# Mozard_2019-08-29.net
KiCad netlist of a schematic drawn in EAGLE
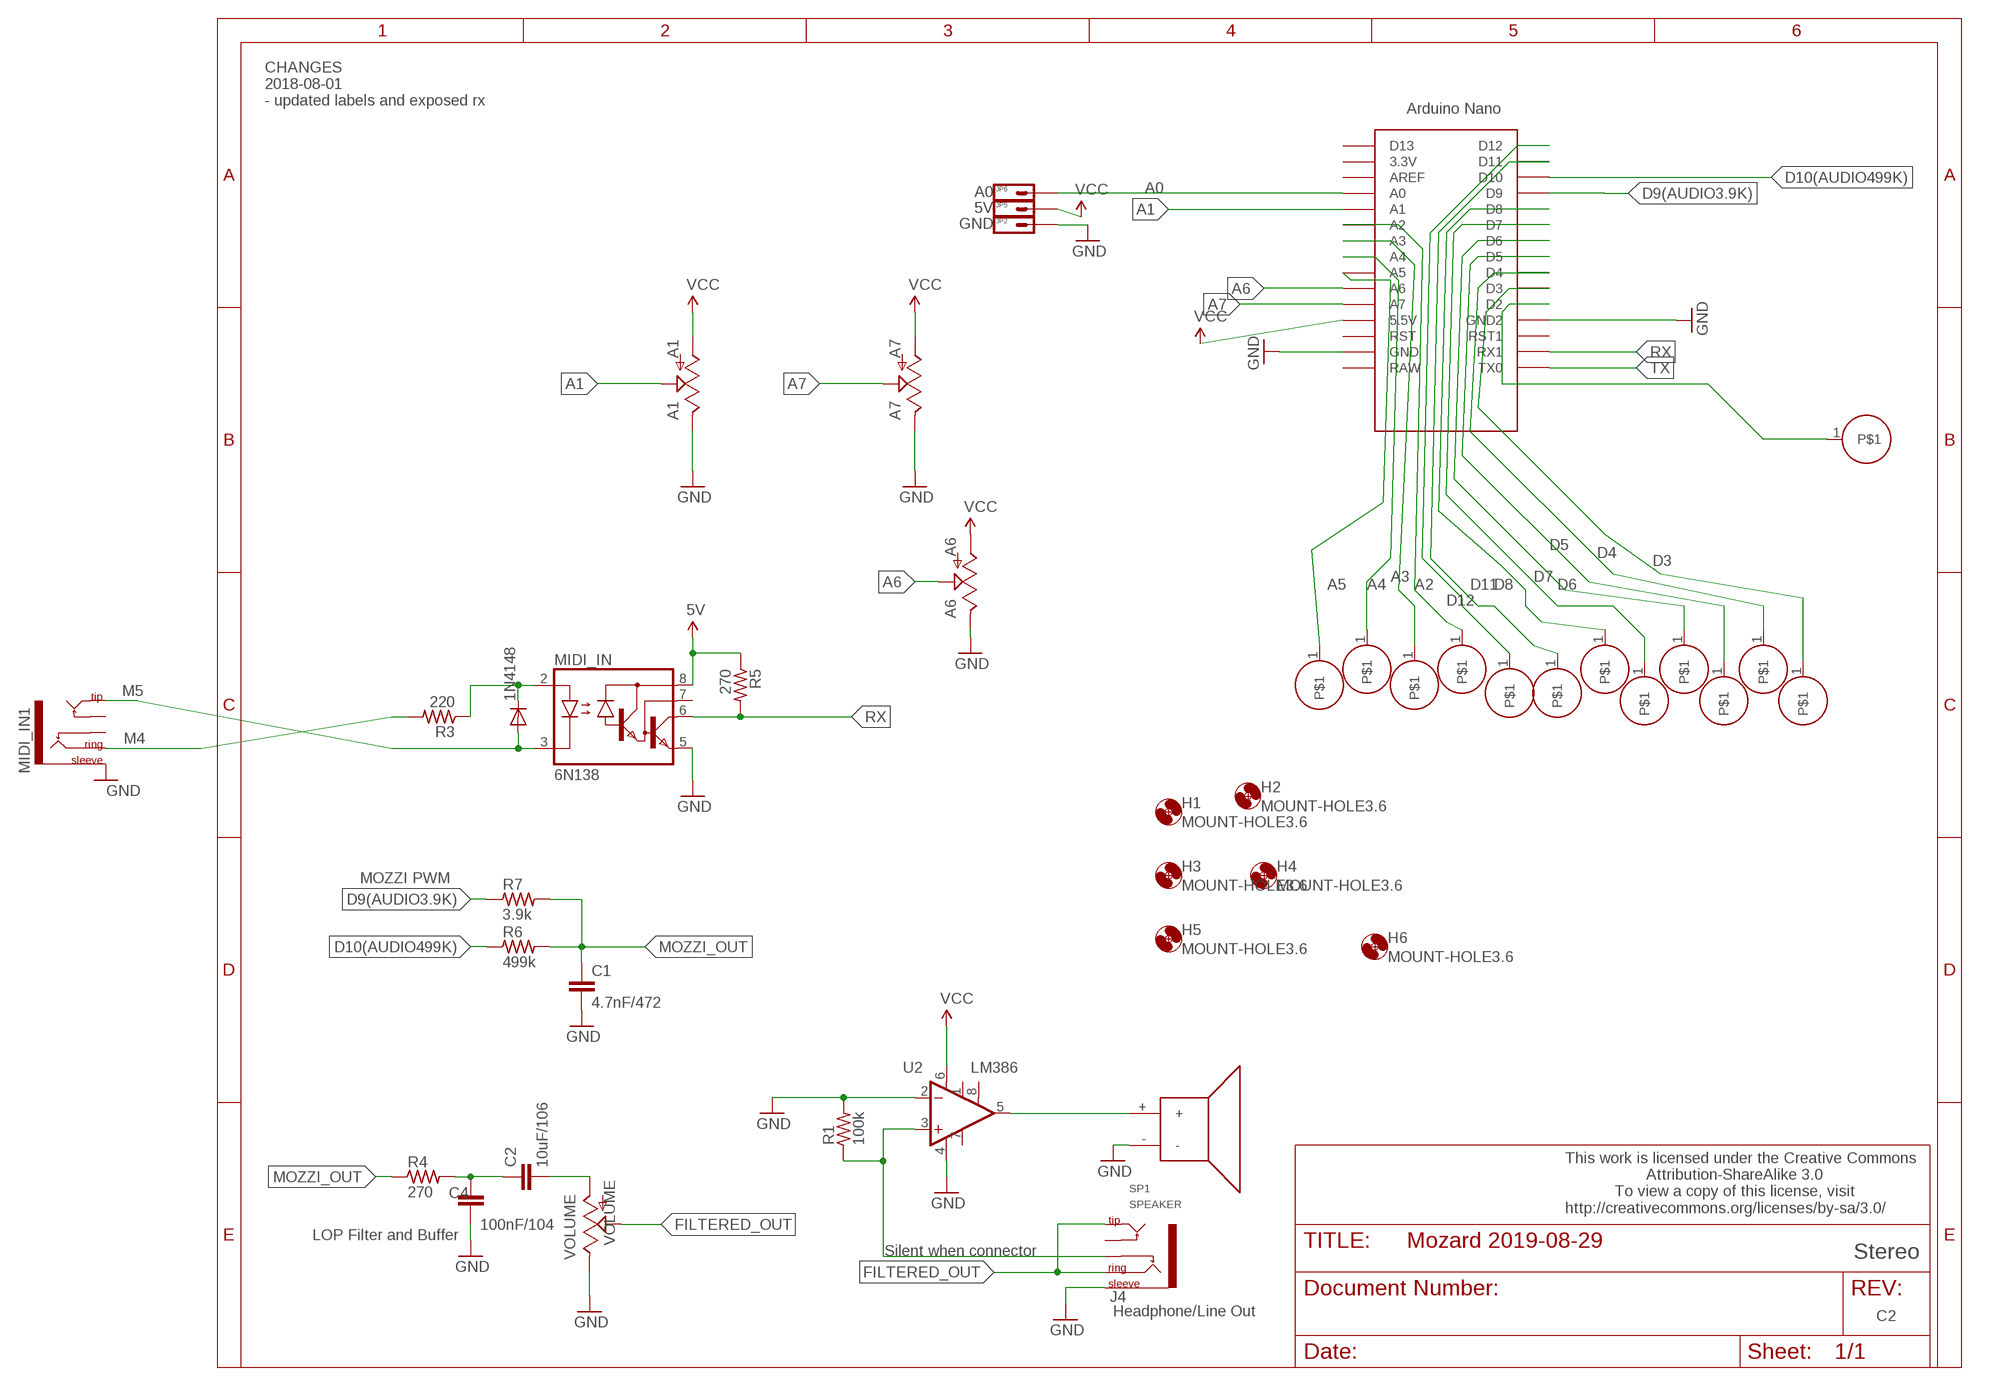
[diagram p0: schematic, sheet 1]

(export (version "E")
  (design (tool "Eeschema 10.0.6"))
  (components
    (comp (ref "1N4148")
      (value "1N4148")
      (footprint "eagle-import:DO41-10")
      (libsource (lib "eagle-import") (part "DIODE"))
    )
    (comp (ref "A1")
      (value "A1")
      (footprint "eagle-import:ALPS_POT")
      (libsource (lib "eagle-import") (part "POT"))
    )
    (comp (ref "A6")
      (value "A6")
      (footprint "eagle-import:ALPS_POT")
      (libsource (lib "eagle-import") (part "POT"))
    )
    (comp (ref "A7")
      (value "A7")
      (footprint "eagle-import:ALPS_POT")
      (libsource (lib "eagle-import") (part "POT"))
    )
    (comp (ref "C1")
      (value "4.7nF/472")
      (footprint "eagle-import:CAP-PTH-SMALL-KIT")
      (libsource (lib "eagle-import") (part "0.1UF-50V-20%(PTH)KIT-EZ"))
    )
    (comp (ref "C2")
      (value "10uF/106")
      (footprint "eagle-import:CAP-PTH-SMALL-KIT")
      (libsource (lib "eagle-import") (part "0.1UF-50V-20%(PTH)KIT-EZ"))
    )
    (comp (ref "C4")
      (value "100nF/104")
      (footprint "eagle-import:CAP-PTH-SMALL-KIT")
      (libsource (lib "eagle-import") (part "0.1UF-50V-20%(PTH)KIT-EZ"))
    )
    (comp (ref "H1")
      (value "MOUNT-HOLE3.6")
      (footprint "eagle-import:3,6")
      (libsource (lib "eagle-import") (part "MOUNT-HOLE3.6"))
    )
    (comp (ref "H2")
      (value "MOUNT-HOLE3.6")
      (footprint "eagle-import:3,6")
      (libsource (lib "eagle-import") (part "MOUNT-HOLE3.6"))
    )
    (comp (ref "H3")
      (value "MOUNT-HOLE3.6")
      (footprint "eagle-import:3,6")
      (libsource (lib "eagle-import") (part "MOUNT-HOLE3.6"))
    )
    (comp (ref "H4")
      (value "MOUNT-HOLE3.6")
      (footprint "eagle-import:3,6")
      (libsource (lib "eagle-import") (part "MOUNT-HOLE3.6"))
    )
    (comp (ref "H5")
      (value "MOUNT-HOLE3.6")
      (footprint "eagle-import:3,6")
      (libsource (lib "eagle-import") (part "MOUNT-HOLE3.6"))
    )
    (comp (ref "H6")
      (value "MOUNT-HOLE3.6")
      (footprint "eagle-import:3,6")
      (libsource (lib "eagle-import") (part "MOUNT-HOLE3.6"))
    )
    (comp (ref "J4")
      (value "Headphone/Line Out")
      (footprint "eagle-import:AUDIO-JACK")
      (libsource (lib "eagle-import") (part "AUDIO-JACKPTH"))
    )
    (comp (ref "JP2")
      (value "GND")
      (footprint "eagle-import:1X01_SIDE_NAME")
      (libsource (lib "eagle-import") (part "HEADER-1X1"))
    )
    (comp (ref "JP5")
      (value "5V")
      (footprint "eagle-import:1X01_SIDE_NAME")
      (libsource (lib "eagle-import") (part "HEADER-1X1"))
    )
    (comp (ref "JP6")
      (value "A0")
      (footprint "eagle-import:1X01_SIDE_NAME")
      (libsource (lib "eagle-import") (part "HEADER-1X1"))
    )
    (comp (ref "MIDI_IN")
      (value "6N138")
      (footprint "eagle-import:DIL08")
      (fields (field (name "MF") "VISHAY/TELEFUNKEN"))
      (libsource (lib "eagle-import") (part "6N138"))
    )
    (comp (ref "MIDI_IN1")
      (value "AUDIO-JACKKIT")
      (footprint "eagle-import:AUDIO-JACK-KIT")
      (libsource (lib "eagle-import") (part "AUDIO-JACKKIT"))
    )
    (comp (ref "R1")
      (value "100k")
      (footprint "eagle-import:0204_7")
      (libsource (lib "eagle-import") (part "R-US_0204/7"))
    )
    (comp (ref "R3")
      (value "220")
      (footprint "eagle-import:0204_5")
      (libsource (lib "eagle-import") (part "R-US_0204/5"))
    )
    (comp (ref "R4")
      (value "270")
      (footprint "eagle-import:0204_7")
      (libsource (lib "eagle-import") (part "R-US_0204/7"))
    )
    (comp (ref "R5")
      (value "270")
      (footprint "eagle-import:0204_5")
      (libsource (lib "eagle-import") (part "R-US_0204/5"))
    )
    (comp (ref "R6")
      (value "499k")
      (footprint "eagle-import:0204_7")
      (libsource (lib "eagle-import") (part "R-US_0204/7"))
    )
    (comp (ref "R7")
      (value "3.9k")
      (footprint "eagle-import:0204_7")
      (libsource (lib "eagle-import") (part "R-US_0204/7"))
    )
    (comp (ref "SP1")
      (value "SPEAKER")
      (footprint "eagle-import:PCB_MOUNT_SPEAKER")
      (fields (field (name "MFG") "SANCO"))
      (libsource (lib "eagle-import") (part "SPEAKERPCB_MOUNT"))
    )
    (comp (ref "U$1")
      (value "NANO")
      (footprint "eagle-import:NANO")
      (libsource (lib "eagle-import") (part "NANO"))
    )
    (comp (ref "U$2")
      (value "PCB-TOUCHPAD-1-PIN")
      (footprint "eagle-import:PCB-TOUCHPAD-1-PIN")
      (libsource (lib "eagle-import") (part "PCB-TOUCHPAD-1-PIN"))
    )
    (comp (ref "U$3")
      (value "PCB-TOUCHPAD-1-PIN")
      (footprint "eagle-import:PCB-TOUCHPAD-1-PIN")
      (libsource (lib "eagle-import") (part "PCB-TOUCHPAD-1-PIN"))
    )
    (comp (ref "U$4")
      (value "PCB-TOUCHPAD-1-PIN")
      (footprint "eagle-import:PCB-TOUCHPAD-1-PIN")
      (libsource (lib "eagle-import") (part "PCB-TOUCHPAD-1-PIN"))
    )
    (comp (ref "U$5")
      (value "PCB-TOUCHPAD-1-PIN")
      (footprint "eagle-import:PCB-TOUCHPAD-1-PIN")
      (libsource (lib "eagle-import") (part "PCB-TOUCHPAD-1-PIN"))
    )
    (comp (ref "U$6")
      (value "PCB-TOUCHPAD-1-PIN")
      (footprint "eagle-import:PCB-TOUCHPAD-1-PIN")
      (libsource (lib "eagle-import") (part "PCB-TOUCHPAD-1-PIN"))
    )
    (comp (ref "U$7")
      (value "PCB-TOUCHPAD-1-PIN")
      (footprint "eagle-import:PCB-TOUCHPAD-1-PIN")
      (libsource (lib "eagle-import") (part "PCB-TOUCHPAD-1-PIN"))
    )
    (comp (ref "U$8")
      (value "PCB-TOUCHPAD-1-PIN")
      (footprint "eagle-import:PCB-TOUCHPAD-1-PIN")
      (libsource (lib "eagle-import") (part "PCB-TOUCHPAD-1-PIN"))
    )
    (comp (ref "U$9")
      (value "PCB-TOUCHPAD-1-PIN")
      (footprint "eagle-import:PCB-TOUCHPAD-1-PIN")
      (libsource (lib "eagle-import") (part "PCB-TOUCHPAD-1-PIN"))
    )
    (comp (ref "U$10")
      (value "PCB-TOUCHPAD-1-PIN")
      (footprint "eagle-import:PCB-TOUCHPAD-1-PIN")
      (libsource (lib "eagle-import") (part "PCB-TOUCHPAD-1-PIN"))
    )
    (comp (ref "U$11")
      (value "PCB-TOUCHPAD-1-PIN")
      (footprint "eagle-import:PCB-TOUCHPAD-1-PIN")
      (libsource (lib "eagle-import") (part "PCB-TOUCHPAD-1-PIN"))
    )
    (comp (ref "U$12")
      (value "PCB-TOUCHPAD-1-PIN")
      (footprint "eagle-import:PCB-TOUCHPAD-1-PIN")
      (libsource (lib "eagle-import") (part "PCB-TOUCHPAD-1-PIN"))
    )
    (comp (ref "U$13")
      (value "PCB-TOUCHPAD-1-PIN")
      (footprint "eagle-import:PCB-TOUCHPAD-1-PIN")
      (libsource (lib "eagle-import") (part "PCB-TOUCHPAD-1-PIN"))
    )
    (comp (ref "U$14")
      (value "PCB-TOUCHPAD-1-PIN")
      (footprint "eagle-import:PCB-TOUCHPAD-1-PIN")
      (libsource (lib "eagle-import") (part "PCB-TOUCHPAD-1-PIN"))
    )
    (comp (ref "U2")
      (value "LM386")
      (footprint "eagle-import:DIP08")
      (libsource (lib "eagle-import") (part "LM386"))
    )
    (comp (ref "VOLUME")
      (value "VOLUME")
      (footprint "eagle-import:ALPS_POT")
      (libsource (lib "eagle-import") (part "POT"))
    )
  )
  (nets
    (net (code "1") (name "/A0") (class "Default")
      (node (ref "JP6") (pin "1") (pinfunction "1_1") (pintype "passive"))
      (node (ref "U$1") (pin "A0") (pinfunction "A0_A0") (pintype "bidirectional"))
    )
    (net (code "2") (name "/A2") (class "Default")
      (node (ref "U$1") (pin "A2") (pinfunction "A2_A2") (pintype "bidirectional"))
      (node (ref "U$5") (pin "1") (pinfunction "P$1_1") (pintype "bidirectional"))
    )
    (net (code "3") (name "/A3") (class "Default")
      (node (ref "U$1") (pin "A3") (pinfunction "A3_A3") (pintype "bidirectional"))
      (node (ref "U$4") (pin "1") (pinfunction "P$1_1") (pintype "bidirectional"))
    )
    (net (code "4") (name "/A4") (class "Default")
      (node (ref "U$1") (pin "A4") (pinfunction "A4_A4") (pintype "bidirectional"))
      (node (ref "U$3") (pin "1") (pinfunction "P$1_1") (pintype "bidirectional"))
    )
    (net (code "5") (name "/A5") (class "Default")
      (node (ref "U$1") (pin "A5") (pinfunction "A5_A5") (pintype "bidirectional"))
      (node (ref "U$2") (pin "1") (pinfunction "P$1_1") (pintype "bidirectional"))
    )
    (net (code "6") (name "/D3") (class "Default")
      (node (ref "U$1") (pin "D3") (pinfunction "D3_D3") (pintype "bidirectional"))
      (node (ref "U$13") (pin "1") (pinfunction "P$1_1") (pintype "bidirectional"))
    )
    (net (code "7") (name "/D4") (class "Default")
      (node (ref "U$1") (pin "D4") (pinfunction "D4_D4") (pintype "bidirectional"))
      (node (ref "U$12") (pin "1") (pinfunction "P$1_1") (pintype "bidirectional"))
    )
    (net (code "8") (name "/D5") (class "Default")
      (node (ref "U$1") (pin "D5") (pinfunction "D5_D5") (pintype "bidirectional"))
      (node (ref "U$11") (pin "1") (pinfunction "P$1_1") (pintype "bidirectional"))
    )
    (net (code "9") (name "/D6") (class "Default")
      (node (ref "U$1") (pin "D6") (pinfunction "D6_D6") (pintype "bidirectional"))
      (node (ref "U$10") (pin "1") (pinfunction "P$1_1") (pintype "bidirectional"))
    )
    (net (code "10") (name "/D7") (class "Default")
      (node (ref "U$1") (pin "D7") (pinfunction "D7_D7") (pintype "bidirectional"))
      (node (ref "U$9") (pin "1") (pinfunction "P$1_1") (pintype "bidirectional"))
    )
    (net (code "11") (name "/D8") (class "Default")
      (node (ref "U$1") (pin "D8") (pinfunction "D8_D8") (pintype "bidirectional"))
      (node (ref "U$8") (pin "1") (pinfunction "P$1_1") (pintype "bidirectional"))
    )
    (net (code "12") (name "/D11") (class "Default")
      (node (ref "U$1") (pin "D11") (pinfunction "D11_D11") (pintype "bidirectional"))
      (node (ref "U$7") (pin "1") (pinfunction "P$1_1") (pintype "bidirectional"))
    )
    (net (code "13") (name "/D12") (class "Default")
      (node (ref "U$1") (pin "D12") (pinfunction "D12_D12") (pintype "bidirectional"))
      (node (ref "U$6") (pin "1") (pinfunction "P$1_1") (pintype "bidirectional"))
    )
    (net (code "14") (name "/M4") (class "Default")
      (node (ref "MIDI_IN1") (pin "RING") (pinfunction "RING_RING") (pintype "bidirectional"))
      (node (ref "R3") (pin "2") (pinfunction "2_2") (pintype "passive"))
    )
    (net (code "15") (name "/M5") (class "Default")
      (node (ref "1N4148") (pin "A") (pinfunction "A_A") (pintype "passive"))
      (node (ref "MIDI_IN") (pin "3") (pinfunction "C_3") (pintype "passive"))
      (node (ref "MIDI_IN1") (pin "TIP") (pinfunction "TIP_TIP") (pintype "bidirectional"))
    )
    (net (code "16") (name "5V") (class "Default")
      (node (ref "MIDI_IN") (pin "8") (pinfunction "VCC_8") (pintype "passive"))
      (node (ref "R5") (pin "1") (pinfunction "1_1") (pintype "passive"))
    )
    (net (code "17") (name "A1") (class "Default")
      (node (ref "A1") (pin "P$2") (pinfunction "S_P$2") (pintype "passive"))
      (node (ref "U$1") (pin "A1") (pinfunction "A1_A1") (pintype "bidirectional"))
    )
    (net (code "18") (name "A6") (class "Default")
      (node (ref "A6") (pin "P$2") (pinfunction "S_P$2") (pintype "passive"))
      (node (ref "U$1") (pin "A6") (pinfunction "A6_A6") (pintype "bidirectional"))
    )
    (net (code "19") (name "A7") (class "Default")
      (node (ref "A7") (pin "P$2") (pinfunction "S_P$2") (pintype "passive"))
      (node (ref "U$1") (pin "A7") (pinfunction "A7_A7") (pintype "bidirectional"))
    )
    (net (code "20") (name "D9(AUDIO3.9K)") (class "Default")
      (node (ref "R7") (pin "1") (pinfunction "1_1") (pintype "passive"))
      (node (ref "U$1") (pin "D9") (pinfunction "D9_D9") (pintype "bidirectional"))
    )
    (net (code "21") (name "D10(AUDIO499K)") (class "Default")
      (node (ref "R6") (pin "1") (pinfunction "1_1") (pintype "passive"))
      (node (ref "U$1") (pin "D10") (pinfunction "D10_D10") (pintype "bidirectional"))
    )
    (net (code "22") (name "FILTERED_OUT") (class "Default")
      (node (ref "J4") (pin "RING") (pinfunction "RING_RING") (pintype "bidirectional"))
      (node (ref "J4") (pin "TIP") (pinfunction "TIP_TIP") (pintype "bidirectional"))
      (node (ref "VOLUME") (pin "P$2") (pinfunction "S_P$2") (pintype "passive"))
    )
    (net (code "23") (name "GND") (class "Default")
      (node (ref "A1") (pin "P$1") (pinfunction "E_P$1") (pintype "passive"))
      (node (ref "A6") (pin "P$1") (pinfunction "E_P$1") (pintype "passive"))
      (node (ref "A7") (pin "P$1") (pinfunction "E_P$1") (pintype "passive"))
      (node (ref "C1") (pin "2") (pinfunction "2_2") (pintype "passive"))
      (node (ref "C4") (pin "2") (pinfunction "2_2") (pintype "passive"))
      (node (ref "J4") (pin "SLEEVE") (pinfunction "SLEEVE_SLEEVE") (pintype "bidirectional"))
      (node (ref "JP2") (pin "1") (pinfunction "1_1") (pintype "passive"))
      (node (ref "MIDI_IN") (pin "5") (pinfunction "GND_5") (pintype "passive"))
      (node (ref "MIDI_IN1") (pin "SLEEVE") (pinfunction "SLEEVE_SLEEVE") (pintype "bidirectional"))
      (node (ref "R1") (pin "2") (pinfunction "2_2") (pintype "passive"))
      (node (ref "SP1") (pin "-") (pinfunction "-_-") (pintype "bidirectional"))
      (node (ref "U$1") (pin "GND") (pinfunction "GND_GND") (pintype "bidirectional"))
      (node (ref "U$1") (pin "GND1") (pinfunction "GND2_GND1") (pintype "bidirectional"))
      (node (ref "U2") (pin "2") (pinfunction "-IN_2") (pintype "input"))
      (node (ref "U2") (pin "4") (pinfunction "V-_4") (pintype "power_in"))
      (node (ref "VOLUME") (pin "P$1") (pinfunction "E_P$1") (pintype "passive"))
    )
    (net (code "24") (name "MOZZI_OUT") (class "Default")
      (node (ref "C1") (pin "1") (pinfunction "1_1") (pintype "passive"))
      (node (ref "R4") (pin "1") (pinfunction "1_1") (pintype "passive"))
      (node (ref "R6") (pin "2") (pinfunction "2_2") (pintype "passive"))
      (node (ref "R7") (pin "2") (pinfunction "2_2") (pintype "passive"))
    )
    (net (code "25") (name "Net-(C2-Pad1)") (class "Default")
      (node (ref "C2") (pin "1") (pinfunction "1_1") (pintype "passive"))
      (node (ref "C4") (pin "1") (pinfunction "1_1") (pintype "passive"))
      (node (ref "R4") (pin "2") (pinfunction "2_2") (pintype "passive"))
    )
    (net (code "26") (name "Net-(MIDI_IN-A)") (class "Default")
      (node (ref "1N4148") (pin "C") (pinfunction "C_C") (pintype "passive"))
      (node (ref "MIDI_IN") (pin "2") (pinfunction "A_2") (pintype "passive"))
      (node (ref "R3") (pin "1") (pinfunction "1_1") (pintype "passive"))
    )
    (net (code "27") (name "Net-(U$14-P$1)") (class "Default")
      (node (ref "U$1") (pin "D2") (pinfunction "D2_D2") (pintype "bidirectional"))
      (node (ref "U$14") (pin "1") (pinfunction "P$1_1") (pintype "bidirectional"))
    )
    (net (code "28") (name "Net-(U2-+IN)") (class "Default")
      (node (ref "J4") (pin "RSH") (pinfunction "RSH_RSH") (pintype "bidirectional"))
      (node (ref "R1") (pin "1") (pinfunction "1_1") (pintype "passive"))
      (node (ref "U2") (pin "3") (pinfunction "+IN_3") (pintype "input"))
    )
    (net (code "29") (name "Net-(U2-OUT)") (class "Default")
      (node (ref "SP1") (pin "+") (pinfunction "+_+") (pintype "bidirectional"))
      (node (ref "U2") (pin "5") (pinfunction "OUT_5") (pintype "output"))
    )
    (net (code "30") (name "Net-(VOLUME-A)") (class "Default")
      (node (ref "C2") (pin "2") (pinfunction "2_2") (pintype "passive"))
      (node (ref "VOLUME") (pin "P$3") (pinfunction "A_P$3") (pintype "passive"))
    )
    (net (code "31") (name "RX") (class "Default")
      (node (ref "MIDI_IN") (pin "6") (pinfunction "VO_6") (pintype "passive"))
      (node (ref "R5") (pin "2") (pinfunction "2_2") (pintype "passive"))
      (node (ref "U$1") (pin "RX1") (pinfunction "RX1_RX1") (pintype "bidirectional"))
    )
    (net (code "32") (name "TX") (class "Default")
      (node (ref "U$1") (pin "TX0") (pinfunction "TX0_TX0") (pintype "bidirectional"))
    )
    (net (code "33") (name "VCC") (class "Default")
      (node (ref "A1") (pin "P$3") (pinfunction "A_P$3") (pintype "passive"))
      (node (ref "A6") (pin "P$3") (pinfunction "A_P$3") (pintype "passive"))
      (node (ref "A7") (pin "P$3") (pinfunction "A_P$3") (pintype "passive"))
      (node (ref "JP5") (pin "1") (pinfunction "1_1") (pintype "passive"))
      (node (ref "U$1") (pin "5V") (pinfunction "5.5V_5V") (pintype "bidirectional"))
      (node (ref "U2") (pin "6") (pinfunction "V+_6") (pintype "power_in"))
    )
    (net (code "34") (name "unconnected-(J4-PadTSH)") (class "Default")
      (node (ref "J4") (pin "TSH") (pinfunction "TSH_TSH") (pintype "bidirectional"))
    )
    (net (code "35") (name "unconnected-(MIDI_IN-VB-Pad7)") (class "Default")
      (node (ref "MIDI_IN") (pin "7") (pinfunction "VB_7") (pintype "passive"))
    )
    (net (code "36") (name "unconnected-(MIDI_IN1-PadRSH)") (class "Default")
      (node (ref "MIDI_IN1") (pin "RSH") (pinfunction "RSH_RSH") (pintype "bidirectional"))
    )
    (net (code "37") (name "unconnected-(MIDI_IN1-PadTSH)") (class "Default")
      (node (ref "MIDI_IN1") (pin "TSH") (pinfunction "TSH_TSH") (pintype "bidirectional"))
    )
    (net (code "38") (name "unconnected-(U$1-Pad3.3V)") (class "Default")
      (node (ref "U$1") (pin "3.3V") (pinfunction "3.3V_3.3V") (pintype "bidirectional"))
    )
    (net (code "39") (name "unconnected-(U$1-PadAREF)") (class "Default")
      (node (ref "U$1") (pin "AREF") (pinfunction "AREF_AREF") (pintype "bidirectional"))
    )
    (net (code "40") (name "unconnected-(U$1-PadD13)") (class "Default")
      (node (ref "U$1") (pin "D13") (pinfunction "D13_D13") (pintype "bidirectional"))
    )
    (net (code "41") (name "unconnected-(U$1-PadRAW)") (class "Default")
      (node (ref "U$1") (pin "RAW") (pinfunction "RAW_RAW") (pintype "bidirectional"))
    )
    (net (code "42") (name "unconnected-(U$1-PadRST)") (class "Default")
      (node (ref "U$1") (pin "RST") (pinfunction "RST_RST") (pintype "bidirectional"))
    )
    (net (code "43") (name "unconnected-(U$1-PadRST1)") (class "Default")
      (node (ref "U$1") (pin "RST1") (pinfunction "RST1_RST1") (pintype "bidirectional"))
    )
    (net (code "44") (name "unconnected-(U2-BP-Pad7)") (class "Default")
      (node (ref "U2") (pin "7") (pinfunction "BP_7") (pintype "bidirectional"))
    )
    (net (code "45") (name "unconnected-(U2-GAIN-Pad1)") (class "Default")
      (node (ref "U2") (pin "1") (pinfunction "GAIN_1") (pintype "bidirectional"))
    )
    (net (code "46") (name "unconnected-(U2-GAIN-Pad8)") (class "Default")
      (node (ref "U2") (pin "8") (pinfunction "GAIN_8") (pintype "bidirectional"))
    )
  )
)
